# 4_Relays_Control.net
KiCad netlist of a schematic drawn in Altium Designer
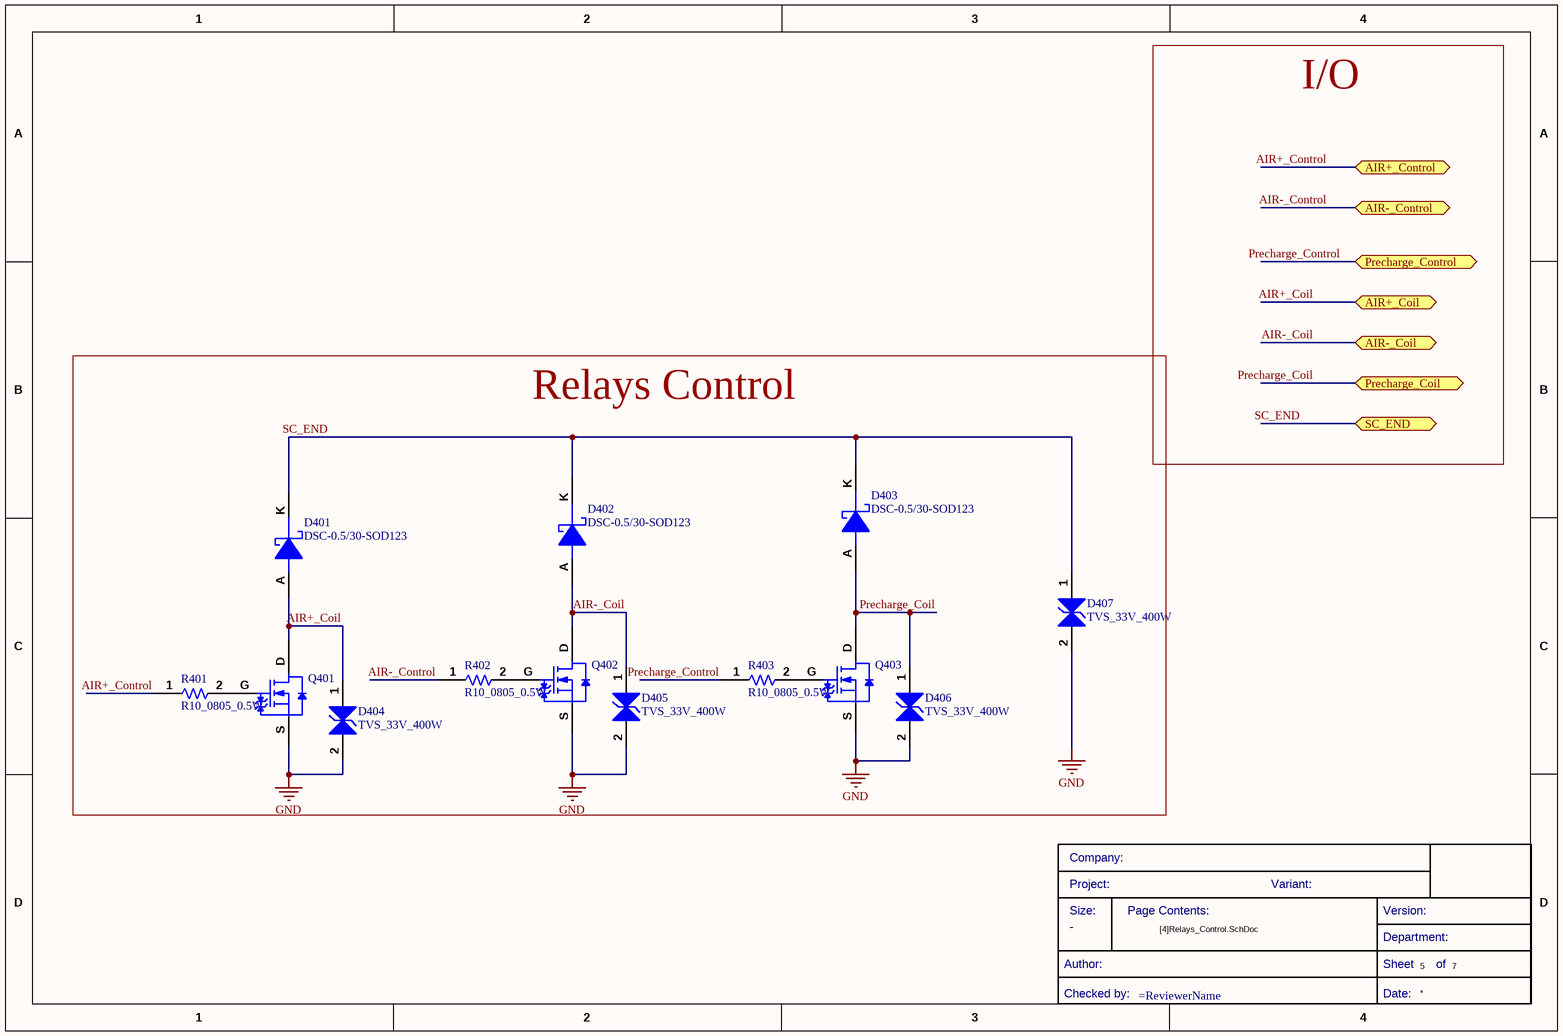
[diagram p0: [4]Relays_Control.SchDoc]

(export (version "E")
  (design (tool "Eeschema 10.0.6"))
  (components
    (comp (ref "D401")
      (value "DSC-0.5/30-SOD123")
      (footprint "DSC-SOD123")
      (description "VR=30V IF=500mA 30pF P=410mW")
      (fields (field (name ".CREATOR") "GP"))
      (libsource (lib "EMEA- E-Tech Racing- I'Escola d'Enginyeria de Barcelona Est") (part "DSC-0.5/30-SOD123"))
    )
    (comp (ref "D402")
      (value "DSC-0.5/30-SOD123")
      (footprint "DSC-SOD123")
      (description "VR=30V IF=500mA 30pF P=410mW")
      (fields (field (name ".CREATOR") "GP"))
      (libsource (lib "EMEA- E-Tech Racing- I'Escola d'Enginyeria de Barcelona Est") (part "DSC-0.5/30-SOD123"))
    )
    (comp (ref "D403")
      (value "DSC-0.5/30-SOD123")
      (footprint "DSC-SOD123")
      (description "VR=30V IF=500mA 30pF P=410mW")
      (fields (field (name ".CREATOR") "GP"))
      (libsource (lib "EMEA- E-Tech Racing- I'Escola d'Enginyeria de Barcelona Est") (part "DSC-0.5/30-SOD123"))
    )
    (comp (ref "D404")
      (value "TVS_33V_400W")
      (footprint "WE-TVSP_DO-214AC_Bidirectional")
      (description "Trans Voltage Suppressor Diode, 400W, Bidirectional, 1 Element, Silicon, DO-214AC")
      (libsource (lib "EMEA- E-Tech Racing- I'Escola d'Enginyeria de Barcelona Est") (part "WE-TVSP_Bidirectional"))
    )
    (comp (ref "D405")
      (value "TVS_33V_400W")
      (footprint "WE-TVSP_DO-214AC_Bidirectional")
      (description "Trans Voltage Suppressor Diode, 400W, Bidirectional, 1 Element, Silicon, DO-214AC")
      (libsource (lib "EMEA- E-Tech Racing- I'Escola d'Enginyeria de Barcelona Est") (part "WE-TVSP_Bidirectional"))
    )
    (comp (ref "D406")
      (value "TVS_33V_400W")
      (footprint "WE-TVSP_DO-214AC_Bidirectional")
      (description "Trans Voltage Suppressor Diode, 400W, Bidirectional, 1 Element, Silicon, DO-214AC")
      (libsource (lib "EMEA- E-Tech Racing- I'Escola d'Enginyeria de Barcelona Est") (part "WE-TVSP_Bidirectional"))
    )
    (comp (ref "D407")
      (value "TVS_33V_400W")
      (footprint "WE-TVSP_DO-214AC_Bidirectional")
      (description "Trans Voltage Suppressor Diode, 400W, Bidirectional, 1 Element, Silicon, DO-214AC")
      (libsource (lib "EMEA- E-Tech Racing- I'Escola d'Enginyeria de Barcelona Est") (part "WE-TVSP_Bidirectional"))
    )
    (comp (ref "Q401")
      (value "SQ2318CES-T1_GE3")
      (footprint "SOT95P245X110-3N")
      (description "Mosfet, N-channel, 40V, 7A, SOT-23 Rohs Compliant: Yes")
      (libsource (lib "EMEA- E-Tech Racing- I'Escola d'Enginyeria de Barcelona Est") (part "TRT-NCH-3/35-CPH"))
    )
    (comp (ref "Q402")
      (value "SQ2318CES-T1_GE3")
      (footprint "SOT95P245X110-3N")
      (description "Mosfet, N-channel, 40V, 7A, SOT-23 Rohs Compliant: Yes")
      (libsource (lib "EMEA- E-Tech Racing- I'Escola d'Enginyeria de Barcelona Est") (part "TRT-NCH-3/35-CPH"))
    )
    (comp (ref "Q403")
      (value "SQ2318CES-T1_GE3")
      (footprint "SOT95P245X110-3N")
      (description "Mosfet, N-channel, 40V, 7A, SOT-23 Rohs Compliant: Yes")
      (libsource (lib "EMEA- E-Tech Racing- I'Escola d'Enginyeria de Barcelona Est") (part "TRT-NCH-3/35-CPH"))
    )
    (comp (ref "R401")
      (value "R10_0805_0.5W")
      (footprint "0805")
      (fields (field (name "TOLERANCE") "1%") (field (name "POWER") "500mW"))
      (libsource (lib "EMEA- E-Tech Racing- I'Escola d'Enginyeria de Barcelona Est") (part "R9.09K-1206FTK"))
    )
    (comp (ref "R402")
      (value "R10_0805_0.5W")
      (footprint "0805")
      (fields (field (name "TOLERANCE") "1%") (field (name "POWER") "500mW"))
      (libsource (lib "EMEA- E-Tech Racing- I'Escola d'Enginyeria de Barcelona Est") (part "R9.09K-1206FTK"))
    )
    (comp (ref "R403")
      (value "R10_0805_0.5W")
      (footprint "0805")
      (fields (field (name "TOLERANCE") "1%") (field (name "POWER") "500mW"))
      (libsource (lib "EMEA- E-Tech Racing- I'Escola d'Enginyeria de Barcelona Est") (part "R9.09K-1206FTK"))
    )
  )
  (nets
    (net (code "1") (name "/AIR+_Coil") (class "Default")
      (node (ref "D401") (pin "A") (pinfunction "A_A") (pintype "passive"))
      (node (ref "D404") (pin "1") (pinfunction "1_1") (pintype "passive"))
      (node (ref "Q401") (pin "D") (pinfunction "D_D") (pintype "passive"))
    )
    (net (code "2") (name "/AIR+_Control") (class "Default")
      (node (ref "R401") (pin "1") (pinfunction "1_1") (pintype "passive"))
    )
    (net (code "3") (name "/AIR-_Coil") (class "Default")
      (node (ref "D402") (pin "A") (pinfunction "A_A") (pintype "passive"))
      (node (ref "D405") (pin "1") (pinfunction "1_1") (pintype "passive"))
      (node (ref "Q402") (pin "D") (pinfunction "D_D") (pintype "passive"))
    )
    (net (code "4") (name "/AIR-_Control") (class "Default")
      (node (ref "R402") (pin "1") (pinfunction "1_1") (pintype "passive"))
    )
    (net (code "5") (name "/Precharge_Coil") (class "Default")
      (node (ref "D403") (pin "A") (pinfunction "A_A") (pintype "passive"))
      (node (ref "D406") (pin "1") (pinfunction "1_1") (pintype "passive"))
      (node (ref "Q403") (pin "D") (pinfunction "D_D") (pintype "passive"))
    )
    (net (code "6") (name "/Precharge_Control") (class "Default")
      (node (ref "R403") (pin "1") (pinfunction "1_1") (pintype "passive"))
    )
    (net (code "7") (name "/SC_END") (class "Default")
      (node (ref "D401") (pin "K") (pinfunction "K_K") (pintype "passive"))
      (node (ref "D402") (pin "K") (pinfunction "K_K") (pintype "passive"))
      (node (ref "D403") (pin "K") (pinfunction "K_K") (pintype "passive"))
      (node (ref "D407") (pin "1") (pinfunction "1_1") (pintype "passive"))
    )
    (net (code "8") (name "GND") (class "Default")
      (node (ref "D404") (pin "2") (pinfunction "2_2") (pintype "passive"))
      (node (ref "D405") (pin "2") (pinfunction "2_2") (pintype "passive"))
      (node (ref "D406") (pin "2") (pinfunction "2_2") (pintype "passive"))
      (node (ref "D407") (pin "2") (pinfunction "2_2") (pintype "passive"))
      (node (ref "Q401") (pin "S") (pinfunction "S_S") (pintype "passive"))
      (node (ref "Q402") (pin "S") (pinfunction "S_S") (pintype "passive"))
      (node (ref "Q403") (pin "S") (pinfunction "S_S") (pintype "passive"))
    )
    (net (code "9") (name "Net-(Q401-PadG)") (class "Default")
      (node (ref "Q401") (pin "G") (pinfunction "G_G") (pintype "passive"))
      (node (ref "R401") (pin "2") (pinfunction "2_2") (pintype "passive"))
    )
    (net (code "10") (name "Net-(Q402-PadG)") (class "Default")
      (node (ref "Q402") (pin "G") (pinfunction "G_G") (pintype "passive"))
      (node (ref "R402") (pin "2") (pinfunction "2_2") (pintype "passive"))
    )
    (net (code "11") (name "Net-(Q403-PadG)") (class "Default")
      (node (ref "Q403") (pin "G") (pinfunction "G_G") (pintype "passive"))
      (node (ref "R403") (pin "2") (pinfunction "2_2") (pintype "passive"))
    )
  )
)
